# 485Driver_MAX3462.net
KiCad netlist of a schematic drawn in Altium Designer
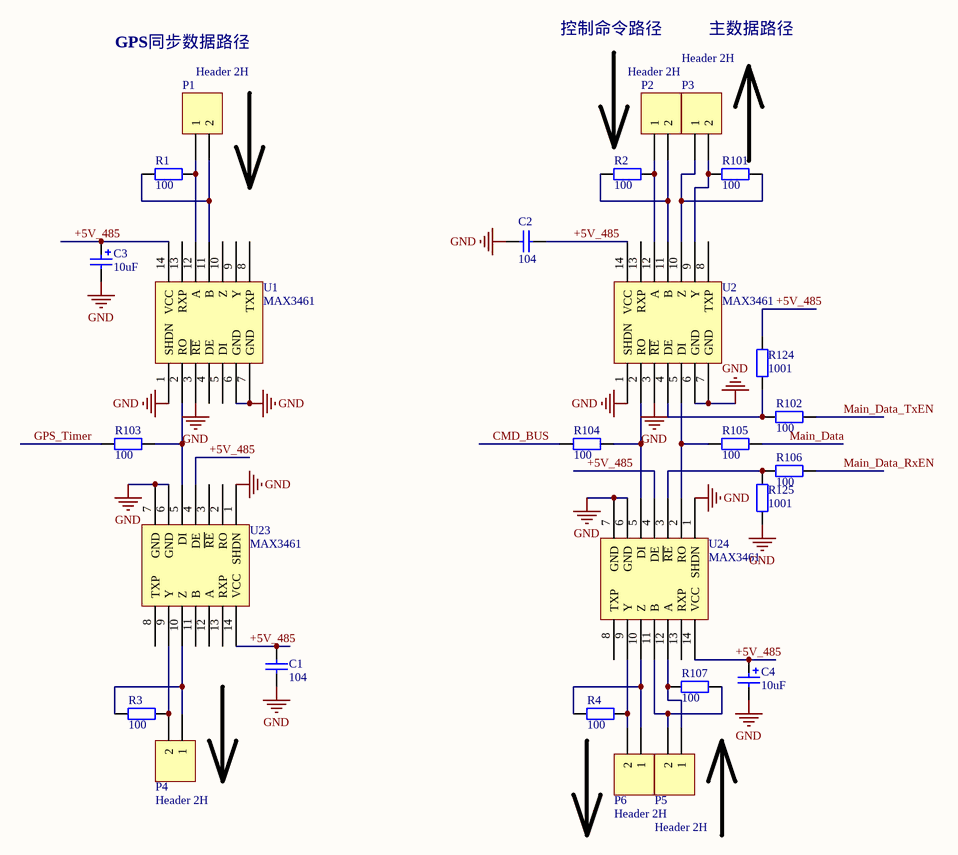
[diagram p0: 485Driver_MAX3462.SchDoc]

(export (version "E")
  (design (tool "Eeschema 10.0.6"))
  (components
    (comp (ref "C1")
      (value "104")
      (footprint "0805C")
      (description "Capacitor")
      (fields (field (name "PUBLISHER") "Altium Limited"))
      (libsource (lib "Miscellaneous Devices") (part "Cap"))
    )
    (comp (ref "C2")
      (value "104")
      (footprint "0805C")
      (description "Capacitor")
      (fields (field (name "PUBLISHER") "Altium Limited"))
      (libsource (lib "Miscellaneous Devices") (part "Cap"))
    )
    (comp (ref "C3")
      (value "10uF")
      (footprint "C68uF")
      (description "Polarized Capacitor (Axial)")
      (fields (field (name "PUBLISHER") "Altium Limited"))
      (libsource (lib "Miscellaneous Devices") (part "Cap Pol2"))
    )
    (comp (ref "C4")
      (value "10uF")
      (footprint "C68uF")
      (description "Polarized Capacitor (Axial)")
      (fields (field (name "PUBLISHER") "Altium Limited"))
      (libsource (lib "Miscellaneous Devices") (part "Cap Pol2"))
    )
    (comp (ref "P1")
      (value "Header 2H")
      (footprint "HDR1X2")
      (description "Header, 2-Pin, Right Angle")
      (fields (field (name "PUBLISHER") "Altium Limited"))
      (libsource (lib "") (part "Header 2H_1"))
    )
    (comp (ref "P2")
      (value "Header 2H")
      (footprint "HDR1X2")
      (description "Header, 2-Pin, Right Angle")
      (fields (field (name "PUBLISHER") "Altium Limited"))
      (libsource (lib "") (part "Header 2H_1"))
    )
    (comp (ref "P3")
      (value "Header 2H")
      (footprint "HDR1X2")
      (description "Header, 2-Pin, Right Angle")
      (fields (field (name "PUBLISHER") "Altium Limited"))
      (libsource (lib "") (part "Header 2H_1"))
    )
    (comp (ref "P4")
      (value "Header 2H")
      (footprint "HDR1X2")
      (description "Header, 2-Pin, Right Angle")
      (fields (field (name "PUBLISHER") "Altium Limited"))
      (libsource (lib "Miscellaneous Connectors") (part "Header 2H"))
    )
    (comp (ref "P5")
      (value "Header 2H")
      (footprint "HDR1X2")
      (description "Header, 2-Pin, Right Angle")
      (fields (field (name "PUBLISHER") "Altium Limited"))
      (libsource (lib "Miscellaneous Connectors") (part "Header 2H"))
    )
    (comp (ref "P6")
      (value "Header 2H")
      (footprint "HDR1X2")
      (description "Header, 2-Pin, Right Angle")
      (fields (field (name "PUBLISHER") "Altium Limited"))
      (libsource (lib "Miscellaneous Connectors") (part "Header 2H"))
    )
    (comp (ref "R1")
      (value "100")
      (footprint "0805R")
      (description "Resistor")
      (fields (field (name "PUBLISHER") "Altium Limited"))
      (libsource (lib "Miscellaneous Devices") (part "Res2"))
    )
    (comp (ref "R2")
      (value "100")
      (footprint "0805R")
      (description "Resistor")
      (fields (field (name "PUBLISHER") "Altium Limited"))
      (libsource (lib "Miscellaneous Devices") (part "Res2"))
    )
    (comp (ref "R3")
      (value "100")
      (footprint "0805R")
      (description "Resistor")
      (fields (field (name "PUBLISHER") "Altium Limited"))
      (libsource (lib "Miscellaneous Devices") (part "Res2"))
    )
    (comp (ref "R4")
      (value "100")
      (footprint "0805R")
      (description "Resistor")
      (fields (field (name "PUBLISHER") "Altium Limited"))
      (libsource (lib "Miscellaneous Devices") (part "Res2"))
    )
    (comp (ref "R101")
      (value "100")
      (footprint "0805R")
      (description "Resistor")
      (fields (field (name "PUBLISHER") "Altium Limited"))
      (libsource (lib "Miscellaneous Devices") (part "Res2"))
    )
    (comp (ref "R102")
      (value "100")
      (footprint "0603")
      (description "Resistor")
      (fields (field (name "PUBLISHER") "Altium Limited"))
      (libsource (lib "Miscellaneous Devices") (part "Res2"))
    )
    (comp (ref "R103")
      (value "100")
      (footprint "0603")
      (description "Resistor")
      (fields (field (name "PUBLISHER") "Altium Limited"))
      (libsource (lib "Miscellaneous Devices") (part "Res2"))
    )
    (comp (ref "R104")
      (value "100")
      (footprint "0603")
      (description "Resistor")
      (fields (field (name "PUBLISHER") "Altium Limited"))
      (libsource (lib "Miscellaneous Devices") (part "Res2"))
    )
    (comp (ref "R105")
      (value "100")
      (footprint "0603")
      (description "Resistor")
      (fields (field (name "PUBLISHER") "Altium Limited"))
      (libsource (lib "Miscellaneous Devices") (part "Res2"))
    )
    (comp (ref "R106")
      (value "100")
      (footprint "0603")
      (description "Resistor")
      (fields (field (name "PUBLISHER") "Altium Limited"))
      (libsource (lib "Miscellaneous Devices") (part "Res2"))
    )
    (comp (ref "R107")
      (value "100")
      (footprint "0805R")
      (description "Resistor")
      (fields (field (name "PUBLISHER") "Altium Limited"))
      (libsource (lib "Miscellaneous Devices") (part "Res2"))
    )
    (comp (ref "R124")
      (value "1001")
      (footprint "0603")
      (description "Resistor")
      (fields (field (name "PUBLISHER") "Altium Limited"))
      (libsource (lib "") (part "Res2_1"))
    )
    (comp (ref "R125")
      (value "1001")
      (footprint "0603")
      (description "Resistor")
      (fields (field (name "PUBLISHER") "Altium Limited"))
      (libsource (lib "") (part "Res2_1"))
    )
    (comp (ref "U1") (value "MAX3461") (footprint "SOP14") (libsource (lib "Schlib1") (part "MAX3461")))
    (comp (ref "U2") (value "MAX3461") (footprint "SOP14") (libsource (lib "Schlib1") (part "MAX3461")))
    (comp (ref "U23") (value "MAX3461") (footprint "SOP14") (libsource (lib "") (part "MAX3461_1")))
    (comp (ref "U24") (value "MAX3461") (footprint "SOP14") (libsource (lib "") (part "MAX3461_1")))
  )
  (nets
    (net (code "1") (name "/+5V_485") (class "Default")
      (node (ref "C1") (pin "2") (pinfunction "2_2") (pintype "passive"))
      (node (ref "C2") (pin "2") (pinfunction "2_2") (pintype "passive"))
      (node (ref "C3") (pin "1") (pinfunction "1_1") (pintype "passive"))
      (node (ref "C4") (pin "1") (pinfunction "1_1") (pintype "passive"))
      (node (ref "R124") (pin "1") (pinfunction "1_1") (pintype "passive"))
      (node (ref "U1") (pin "14") (pinfunction "VCC_14") (pintype "passive"))
      (node (ref "U2") (pin "14") (pinfunction "VCC_14") (pintype "passive"))
      (node (ref "U23") (pin "14") (pinfunction "VCC_14") (pintype "passive"))
      (node (ref "U23") (pin "4") (pinfunction "DE_4") (pintype "passive"))
      (node (ref "U24") (pin "14") (pinfunction "VCC_14") (pintype "passive"))
      (node (ref "U24") (pin "4") (pinfunction "DE_4") (pintype "passive"))
    )
    (net (code "2") (name "/CMD_BUS") (class "Default")
      (node (ref "R104") (pin "2") (pinfunction "2_2") (pintype "passive"))
    )
    (net (code "3") (name "/GPS_Timer") (class "Default")
      (node (ref "R103") (pin "2") (pinfunction "2_2") (pintype "passive"))
    )
    (net (code "4") (name "/Main_Data") (class "Default")
      (node (ref "R105") (pin "1") (pinfunction "1_1") (pintype "passive"))
    )
    (net (code "5") (name "/Main_Data_RxEN") (class "Default")
      (node (ref "R106") (pin "1") (pinfunction "1_1") (pintype "passive"))
    )
    (net (code "6") (name "/Main_Data_TxEN") (class "Default")
      (node (ref "R102") (pin "1") (pinfunction "1_1") (pintype "passive"))
    )
    (net (code "7") (name "GND") (class "Default")
      (node (ref "C1") (pin "1") (pinfunction "1_1") (pintype "passive"))
      (node (ref "C2") (pin "1") (pinfunction "1_1") (pintype "passive"))
      (node (ref "C3") (pin "2") (pinfunction "2_2") (pintype "passive"))
      (node (ref "C4") (pin "2") (pinfunction "2_2") (pintype "passive"))
      (node (ref "R125") (pin "2") (pinfunction "2_2") (pintype "passive"))
      (node (ref "U1") (pin "1") (pinfunction "SHDN_1") (pintype "passive"))
      (node (ref "U1") (pin "3") (pinfunction "~{RE}_3") (pintype "passive"))
      (node (ref "U1") (pin "6") (pinfunction "GND_6") (pintype "passive"))
      (node (ref "U1") (pin "7") (pinfunction "GND_7") (pintype "passive"))
      (node (ref "U2") (pin "1") (pinfunction "SHDN_1") (pintype "passive"))
      (node (ref "U2") (pin "3") (pinfunction "~{RE}_3") (pintype "passive"))
      (node (ref "U2") (pin "6") (pinfunction "GND_6") (pintype "passive"))
      (node (ref "U2") (pin "7") (pinfunction "GND_7") (pintype "passive"))
      (node (ref "U23") (pin "1") (pinfunction "SHDN_1") (pintype "passive"))
      (node (ref "U23") (pin "6") (pinfunction "GND_6") (pintype "passive"))
      (node (ref "U23") (pin "7") (pinfunction "GND_7") (pintype "passive"))
      (node (ref "U24") (pin "1") (pinfunction "SHDN_1") (pintype "passive"))
      (node (ref "U24") (pin "6") (pinfunction "GND_6") (pintype "passive"))
      (node (ref "U24") (pin "7") (pinfunction "GND_7") (pintype "passive"))
    )
    (net (code "8") (name "Net-(U1-A)") (class "Default")
      (node (ref "P1") (pin "1") (pinfunction "1_1") (pintype "passive"))
      (node (ref "R1") (pin "1") (pinfunction "1_1") (pintype "passive"))
      (node (ref "U1") (pin "12") (pinfunction "A_12") (pintype "passive"))
    )
    (net (code "9") (name "Net-(U1-B)") (class "Default")
      (node (ref "P1") (pin "2") (pinfunction "2_2") (pintype "passive"))
      (node (ref "R1") (pin "2") (pinfunction "2_2") (pintype "passive"))
      (node (ref "U1") (pin "11") (pinfunction "B_11") (pintype "passive"))
    )
    (net (code "10") (name "Net-(U1-RO)") (class "Default")
      (node (ref "R103") (pin "1") (pinfunction "1_1") (pintype "passive"))
      (node (ref "U1") (pin "2") (pinfunction "RO_2") (pintype "passive"))
      (node (ref "U23") (pin "5") (pinfunction "DI_5") (pintype "passive"))
    )
    (net (code "11") (name "Net-(U2-A)") (class "Default")
      (node (ref "P2") (pin "1") (pinfunction "1_1") (pintype "passive"))
      (node (ref "R2") (pin "1") (pinfunction "1_1") (pintype "passive"))
      (node (ref "U2") (pin "12") (pinfunction "A_12") (pintype "passive"))
    )
    (net (code "12") (name "Net-(U2-B)") (class "Default")
      (node (ref "P2") (pin "2") (pinfunction "2_2") (pintype "passive"))
      (node (ref "R2") (pin "2") (pinfunction "2_2") (pintype "passive"))
      (node (ref "U2") (pin "11") (pinfunction "B_11") (pintype "passive"))
    )
    (net (code "13") (name "Net-(U2-DE)") (class "Default")
      (node (ref "R102") (pin "2") (pinfunction "2_2") (pintype "passive"))
      (node (ref "R124") (pin "2") (pinfunction "2_2") (pintype "passive"))
      (node (ref "U2") (pin "4") (pinfunction "DE_4") (pintype "passive"))
    )
    (net (code "14") (name "Net-(U2-DI)") (class "Default")
      (node (ref "R105") (pin "2") (pinfunction "2_2") (pintype "passive"))
      (node (ref "U2") (pin "5") (pinfunction "DI_5") (pintype "passive"))
      (node (ref "U24") (pin "2") (pinfunction "RO_2") (pintype "passive"))
    )
    (net (code "15") (name "Net-(U2-RO)") (class "Default")
      (node (ref "R104") (pin "1") (pinfunction "1_1") (pintype "passive"))
      (node (ref "U2") (pin "2") (pinfunction "RO_2") (pintype "passive"))
      (node (ref "U24") (pin "5") (pinfunction "DI_5") (pintype "passive"))
    )
    (net (code "16") (name "Net-(U2-Y)") (class "Default")
      (node (ref "P3") (pin "2") (pinfunction "2_2") (pintype "passive"))
      (node (ref "R101") (pin "2") (pinfunction "2_2") (pintype "passive"))
      (node (ref "U2") (pin "9") (pinfunction "Y_9") (pintype "passive"))
    )
    (net (code "17") (name "Net-(U2-Z)") (class "Default")
      (node (ref "P3") (pin "1") (pinfunction "1_1") (pintype "passive"))
      (node (ref "R101") (pin "1") (pinfunction "1_1") (pintype "passive"))
      (node (ref "U2") (pin "10") (pinfunction "Z_10") (pintype "passive"))
    )
    (net (code "18") (name "Net-(U23-Y)") (class "Default")
      (node (ref "P4") (pin "2") (pinfunction "2_2") (pintype "passive"))
      (node (ref "R3") (pin "1") (pinfunction "1_1") (pintype "passive"))
      (node (ref "U23") (pin "9") (pinfunction "Y_9") (pintype "passive"))
    )
    (net (code "19") (name "Net-(U23-Z)") (class "Default")
      (node (ref "P4") (pin "1") (pinfunction "1_1") (pintype "passive"))
      (node (ref "R3") (pin "2") (pinfunction "2_2") (pintype "passive"))
      (node (ref "U23") (pin "10") (pinfunction "Z_10") (pintype "passive"))
    )
    (net (code "20") (name "Net-(U24-A)") (class "Default")
      (node (ref "P5") (pin "1") (pinfunction "1_1") (pintype "passive"))
      (node (ref "R107") (pin "2") (pinfunction "2_2") (pintype "passive"))
      (node (ref "U24") (pin "12") (pinfunction "A_12") (pintype "passive"))
    )
    (net (code "21") (name "Net-(U24-B)") (class "Default")
      (node (ref "P5") (pin "2") (pinfunction "2_2") (pintype "passive"))
      (node (ref "R107") (pin "1") (pinfunction "1_1") (pintype "passive"))
      (node (ref "U24") (pin "11") (pinfunction "B_11") (pintype "passive"))
    )
    (net (code "22") (name "Net-(U24-Y)") (class "Default")
      (node (ref "P6") (pin "2") (pinfunction "2_2") (pintype "passive"))
      (node (ref "R4") (pin "1") (pinfunction "1_1") (pintype "passive"))
      (node (ref "U24") (pin "9") (pinfunction "Y_9") (pintype "passive"))
    )
    (net (code "23") (name "Net-(U24-Z)") (class "Default")
      (node (ref "P6") (pin "1") (pinfunction "1_1") (pintype "passive"))
      (node (ref "R4") (pin "2") (pinfunction "2_2") (pintype "passive"))
      (node (ref "U24") (pin "10") (pinfunction "Z_10") (pintype "passive"))
    )
    (net (code "24") (name "Net-(U24-~{RE})") (class "Default")
      (node (ref "R106") (pin "2") (pinfunction "2_2") (pintype "passive"))
      (node (ref "R125") (pin "1") (pinfunction "1_1") (pintype "passive"))
      (node (ref "U24") (pin "3") (pinfunction "~{RE}_3") (pintype "passive"))
    )
    (net (code "25") (name "unconnected-(U1-DE-Pad4)") (class "Default")
      (node (ref "U1") (pin "4") (pinfunction "DE_4") (pintype "passive"))
    )
    (net (code "26") (name "unconnected-(U1-DI-Pad5)") (class "Default")
      (node (ref "U1") (pin "5") (pinfunction "DI_5") (pintype "passive"))
    )
    (net (code "27") (name "unconnected-(U1-RXP-Pad13)") (class "Default")
      (node (ref "U1") (pin "13") (pinfunction "RXP_13") (pintype "passive"))
    )
    (net (code "28") (name "unconnected-(U1-TXP-Pad8)") (class "Default")
      (node (ref "U1") (pin "8") (pinfunction "TXP_8") (pintype "passive"))
    )
    (net (code "29") (name "unconnected-(U1-Y-Pad9)") (class "Default")
      (node (ref "U1") (pin "9") (pinfunction "Y_9") (pintype "passive"))
    )
    (net (code "30") (name "unconnected-(U1-Z-Pad10)") (class "Default")
      (node (ref "U1") (pin "10") (pinfunction "Z_10") (pintype "passive"))
    )
    (net (code "31") (name "unconnected-(U2-RXP-Pad13)") (class "Default")
      (node (ref "U2") (pin "13") (pinfunction "RXP_13") (pintype "passive"))
    )
    (net (code "32") (name "unconnected-(U2-TXP-Pad8)") (class "Default")
      (node (ref "U2") (pin "8") (pinfunction "TXP_8") (pintype "passive"))
    )
    (net (code "33") (name "unconnected-(U23-A-Pad12)") (class "Default")
      (node (ref "U23") (pin "12") (pinfunction "A_12") (pintype "passive"))
    )
    (net (code "34") (name "unconnected-(U23-B-Pad11)") (class "Default")
      (node (ref "U23") (pin "11") (pinfunction "B_11") (pintype "passive"))
    )
    (net (code "35") (name "unconnected-(U23-RO-Pad2)") (class "Default")
      (node (ref "U23") (pin "2") (pinfunction "RO_2") (pintype "passive"))
    )
    (net (code "36") (name "unconnected-(U23-RXP-Pad13)") (class "Default")
      (node (ref "U23") (pin "13") (pinfunction "RXP_13") (pintype "passive"))
    )
    (net (code "37") (name "unconnected-(U23-TXP-Pad8)") (class "Default")
      (node (ref "U23") (pin "8") (pinfunction "TXP_8") (pintype "passive"))
    )
    (net (code "38") (name "unconnected-(U23-~{RE}-Pad3)") (class "Default")
      (node (ref "U23") (pin "3") (pinfunction "~{RE}_3") (pintype "passive"))
    )
    (net (code "39") (name "unconnected-(U24-RXP-Pad13)") (class "Default")
      (node (ref "U24") (pin "13") (pinfunction "RXP_13") (pintype "passive"))
    )
    (net (code "40") (name "unconnected-(U24-TXP-Pad8)") (class "Default")
      (node (ref "U24") (pin "8") (pinfunction "TXP_8") (pintype "passive"))
    )
  )
)
